# 30x70-motor-controller-0_2.net
KiCad netlist of a schematic drawn in EAGLE
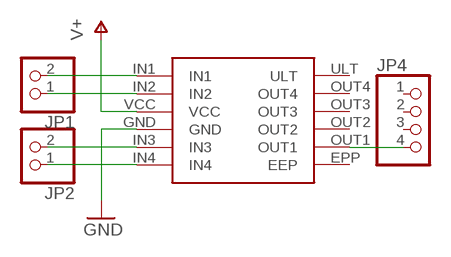
[diagram p0: schematic, sheet 1]
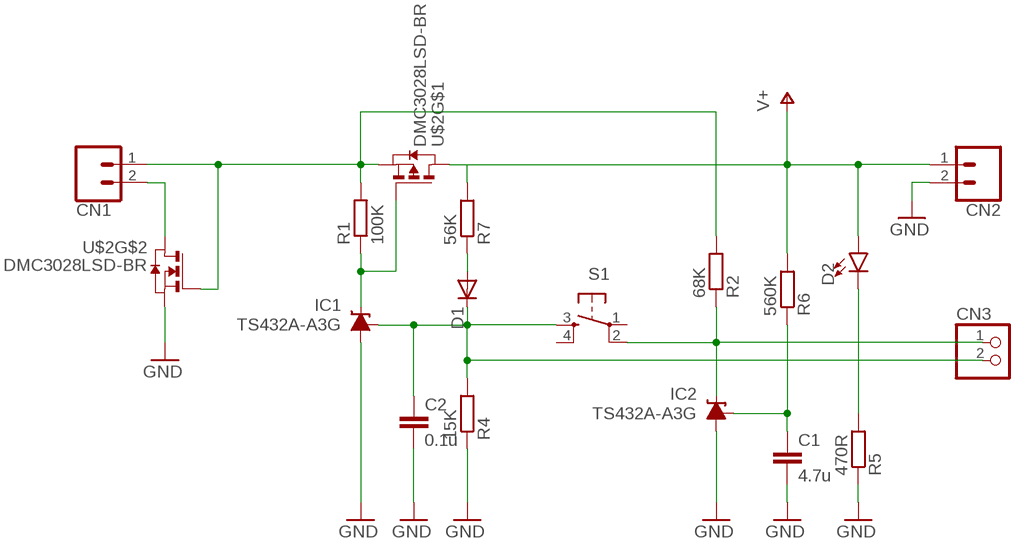
[diagram p1: schematic, sheet 2]

(export (version "E")
  (design (tool "Eeschema 10.0.6"))
  (components
    (comp (ref "JP1")
      (value "PINHD-1X2/90")
      (footprint "eagle-import:1X02_90")
      (libsource (lib "eagle-import") (part "PINHD-1X2/90"))
    )
    (comp (ref "JP2")
      (value "PINHD-1X2/90")
      (footprint "eagle-import:1X02_90")
      (libsource (lib "eagle-import") (part "PINHD-1X2/90"))
    )
    (comp (ref "JP4")
      (value "PINHD-1X4/90")
      (footprint "eagle-import:1X04_90")
      (libsource (lib "eagle-import") (part "PINHD-1X4/90"))
    )
    (comp (ref "U$1")
      (value "DRV8833-MODULE")
      (footprint "eagle-import:DRV8833-BRKOUT")
      (libsource (lib "eagle-import") (part "DRV8833-MODULE"))
    )
    (comp (ref "C1")
      (value "4.7u")
      (footprint "eagle-import:C025-025X050")
      (libsource (lib "eagle-import") (part "C-EU025-025X050"))
    )
    (comp (ref "C2")
      (value "0.1u")
      (footprint "eagle-import:C025-024X044")
      (libsource (lib "eagle-import") (part "C-EU025-024X044"))
    )
    (comp (ref "CN1")
      (value "CONN_02-JST-XTH")
      (footprint "eagle-import:JST-2-XTH")
      (libsource (lib "eagle-import") (part "CONN_02-JST-XTH"))
    )
    (comp (ref "CN2")
      (value "CONN_02-JST-XTH")
      (footprint "eagle-import:JST-2-XTH")
      (libsource (lib "eagle-import") (part "CONN_02-JST-XTH"))
    )
    (comp (ref "CN3")
      (value "PINHD-1X2/90")
      (footprint "eagle-import:1X02_90")
      (libsource (lib "eagle-import") (part "PINHD-1X2/90"))
    )
    (comp (ref "D1")
      (value "DIODE-D-2.5")
      (footprint "eagle-import:D-2.5")
      (libsource (lib "eagle-import") (part "DIODE-D-2.5"))
    )
    (comp (ref "D2")
      (value "LED-3MM-NO_SILK")
      (footprint "eagle-import:LED_3MM-NS")
      (libsource (lib "eagle-import") (part "LED-3MM-NO_SILK"))
    )
    (comp (ref "IC1")
      (value "TS432A-A3G")
      (footprint "eagle-import:TO92-LINE")
      (libsource (lib "eagle-import") (part "TS432A-A3G"))
    )
    (comp (ref "IC2")
      (value "TS432A-A3G")
      (footprint "eagle-import:TO92-LINE")
      (libsource (lib "eagle-import") (part "TS432A-A3G"))
    )
    (comp (ref "R1")
      (value "100K")
      (footprint "eagle-import:0204V")
      (libsource (lib "eagle-import") (part "R-EU_0204/2V"))
    )
    (comp (ref "R2")
      (value "68K")
      (footprint "eagle-import:0207_15")
      (libsource (lib "eagle-import") (part "R-EU_0207/15"))
    )
    (comp (ref "R4")
      (value "15K")
      (footprint "eagle-import:0204V")
      (libsource (lib "eagle-import") (part "R-EU_0204/2V"))
    )
    (comp (ref "R5")
      (value "470R")
      (footprint "eagle-import:0204V")
      (libsource (lib "eagle-import") (part "R-EU_0204/2V"))
    )
    (comp (ref "R6")
      (value "560K")
      (footprint "eagle-import:0204V")
      (libsource (lib "eagle-import") (part "R-EU_0204/2V"))
    )
    (comp (ref "R7")
      (value "56K")
      (footprint "eagle-import:0204_7")
      (libsource (lib "eagle-import") (part "R-EU_0204/7"))
    )
    (comp (ref "S1")
      (value "PROTO-MICRO-SWITCH")
      (footprint "eagle-import:B3F-10XX-PROTO")
      (libsource (lib "eagle-import") (part "PROTO-MICRO-SWITCH"))
    )
    (comp (ref "U$2")
      (value "DMC3028LSD-BR")
      (footprint "eagle-import:DIL8-BREAKOUT")
      (libsource (lib "eagle-import") (part "DMC3028LSD-BR"))
    )
  )
  (nets
    (net (code "1") (name "GND") (class "Default")
      (node (ref "C1") (pin "2") (pinfunction "2_2") (pintype "passive"))
      (node (ref "C2") (pin "2") (pinfunction "2_2") (pintype "passive"))
      (node (ref "CN2") (pin "2") (pinfunction "2_2") (pintype "passive"))
      (node (ref "IC1") (pin "2") (pinfunction "A_2") (pintype "passive"))
      (node (ref "IC2") (pin "2") (pinfunction "A_2") (pintype "passive"))
      (node (ref "R4") (pin "1") (pinfunction "1_1") (pintype "passive"))
      (node (ref "R5") (pin "1") (pinfunction "1_1") (pintype "passive"))
      (node (ref "U$1") (pin "GND") (pinfunction "GND_GND") (pintype "bidirectional"))
      (node (ref "U$2") (pin "1") (pinfunction "S_1") (pintype "passive"))
    )
    (net (code "2") (name "Net-(CN1-Pad2)") (class "Default")
      (node (ref "CN1") (pin "2") (pinfunction "2_2") (pintype "passive"))
      (node (ref "U$2") (pin "7") (pinfunction "D_7") (pintype "passive"))
      (node (ref "U$2") (pin "8") (pinfunction "D_8") (pintype "passive"))
    )
    (net (code "3") (name "Net-(D1-PadA)") (class "Default")
      (node (ref "D1") (pin "A") (pinfunction "A_A") (pintype "passive"))
      (node (ref "R7") (pin "1") (pinfunction "1_1") (pintype "passive"))
    )
    (net (code "4") (name "Net-(D2-C)") (class "Default")
      (node (ref "D2") (pin "K") (pinfunction "C_K") (pintype "passive"))
      (node (ref "R5") (pin "2") (pinfunction "2_2") (pintype "passive"))
    )
    (net (code "5") (name "Net-(IC1-C)") (class "Default")
      (node (ref "IC1") (pin "1") (pinfunction "C_1") (pintype "passive"))
      (node (ref "R1") (pin "1") (pinfunction "1_1") (pintype "passive"))
      (node (ref "U$2") (pin "4") (pinfunction "G_4") (pintype "passive"))
    )
    (net (code "6") (name "Net-(IC1-FB)") (class "Default")
      (node (ref "C2") (pin "1") (pinfunction "1_1") (pintype "passive"))
      (node (ref "CN3") (pin "2") (pinfunction "2_2") (pintype "passive"))
      (node (ref "D1") (pin "C") (pinfunction "C_C") (pintype "passive"))
      (node (ref "IC1") (pin "3") (pinfunction "FB_3") (pintype "passive"))
      (node (ref "R4") (pin "2") (pinfunction "2_2") (pintype "passive"))
      (node (ref "S1") (pin "3") (pinfunction "S_3") (pintype "passive"))
    )
    (net (code "7") (name "Net-(IC2-C)") (class "Default")
      (node (ref "CN3") (pin "1") (pinfunction "1_1") (pintype "passive"))
      (node (ref "IC2") (pin "1") (pinfunction "C_1") (pintype "passive"))
      (node (ref "R2") (pin "1") (pinfunction "1_1") (pintype "passive"))
      (node (ref "S1") (pin "2") (pinfunction "P1_2") (pintype "passive"))
    )
    (net (code "8") (name "Net-(IC2-FB)") (class "Default")
      (node (ref "C1") (pin "1") (pinfunction "1_1") (pintype "passive"))
      (node (ref "IC2") (pin "3") (pinfunction "FB_3") (pintype "passive"))
      (node (ref "R6") (pin "1") (pinfunction "1_1") (pintype "passive"))
    )
    (net (code "9") (name "Net-(JP1-Pad1)") (class "Default")
      (node (ref "JP1") (pin "1") (pinfunction "1_1") (pintype "passive"))
      (node (ref "U$1") (pin "IN2") (pinfunction "IN2_IN2") (pintype "bidirectional"))
    )
    (net (code "10") (name "Net-(JP1-Pad2)") (class "Default")
      (node (ref "JP1") (pin "2") (pinfunction "2_2") (pintype "passive"))
      (node (ref "U$1") (pin "IN1") (pinfunction "IN1_IN1") (pintype "bidirectional"))
    )
    (net (code "11") (name "Net-(JP2-Pad1)") (class "Default")
      (node (ref "JP2") (pin "1") (pinfunction "1_1") (pintype "passive"))
      (node (ref "U$1") (pin "IN4") (pinfunction "IN4_IN4") (pintype "bidirectional"))
    )
    (net (code "12") (name "Net-(JP2-Pad2)") (class "Default")
      (node (ref "JP2") (pin "2") (pinfunction "2_2") (pintype "passive"))
      (node (ref "U$1") (pin "IN3") (pinfunction "IN3_IN3") (pintype "bidirectional"))
    )
    (net (code "13") (name "Net-(JP4-Pad4)") (class "Default")
      (node (ref "JP4") (pin "4") (pinfunction "4_4") (pintype "passive"))
      (node (ref "U$1") (pin "OUT1") (pinfunction "OUT1_OUT1") (pintype "bidirectional"))
    )
    (net (code "14") (name "Net-(U$2A-S)") (class "Default")
      (node (ref "CN1") (pin "1") (pinfunction "1_1") (pintype "passive"))
      (node (ref "R1") (pin "2") (pinfunction "2_2") (pintype "passive"))
      (node (ref "R2") (pin "2") (pinfunction "2_2") (pintype "passive"))
      (node (ref "U$2") (pin "2") (pinfunction "G_2") (pintype "passive"))
      (node (ref "U$2") (pin "3") (pinfunction "S_3") (pintype "passive"))
    )
    (net (code "15") (name "V+") (class "Default")
      (node (ref "CN2") (pin "1") (pinfunction "1_1") (pintype "passive"))
      (node (ref "D2") (pin "A") (pinfunction "A_A") (pintype "passive"))
      (node (ref "R6") (pin "2") (pinfunction "2_2") (pintype "passive"))
      (node (ref "R7") (pin "2") (pinfunction "2_2") (pintype "passive"))
      (node (ref "U$1") (pin "VCC") (pinfunction "VCC_VCC") (pintype "bidirectional"))
      (node (ref "U$2") (pin "5") (pinfunction "D_5") (pintype "passive"))
      (node (ref "U$2") (pin "6") (pinfunction "D_6") (pintype "passive"))
    )
    (net (code "16") (name "unconnected-(JP4-Pad1)") (class "Default")
      (node (ref "JP4") (pin "1") (pinfunction "1_1") (pintype "passive"))
    )
    (net (code "17") (name "unconnected-(JP4-Pad2)") (class "Default")
      (node (ref "JP4") (pin "2") (pinfunction "2_2") (pintype "passive"))
    )
    (net (code "18") (name "unconnected-(JP4-Pad3)") (class "Default")
      (node (ref "JP4") (pin "3") (pinfunction "3_3") (pintype "passive"))
    )
    (net (code "19") (name "unconnected-(S1-P-Pad1)") (class "Default")
      (node (ref "S1") (pin "1") (pinfunction "P_1") (pintype "passive"))
    )
    (net (code "20") (name "unconnected-(S1-S1-Pad4)") (class "Default")
      (node (ref "S1") (pin "4") (pinfunction "S1_4") (pintype "passive"))
    )
    (net (code "21") (name "unconnected-(U$1-EEP-PadEPP)") (class "Default")
      (node (ref "U$1") (pin "EPP") (pinfunction "EEP_EPP") (pintype "bidirectional"))
    )
    (net (code "22") (name "unconnected-(U$1-PadOUT2)") (class "Default")
      (node (ref "U$1") (pin "OUT2") (pinfunction "OUT2_OUT2") (pintype "bidirectional"))
    )
    (net (code "23") (name "unconnected-(U$1-PadOUT3)") (class "Default")
      (node (ref "U$1") (pin "OUT3") (pinfunction "OUT3_OUT3") (pintype "bidirectional"))
    )
    (net (code "24") (name "unconnected-(U$1-PadOUT4)") (class "Default")
      (node (ref "U$1") (pin "OUT4") (pinfunction "OUT4_OUT4") (pintype "bidirectional"))
    )
    (net (code "25") (name "unconnected-(U$1-PadULT)") (class "Default")
      (node (ref "U$1") (pin "ULT") (pinfunction "ULT_ULT") (pintype "bidirectional"))
    )
  )
)
